# SCH_Smart-Traffic-Light_2025-03-28_1.net
KiCad netlist of a schematic drawn in EasyEDA
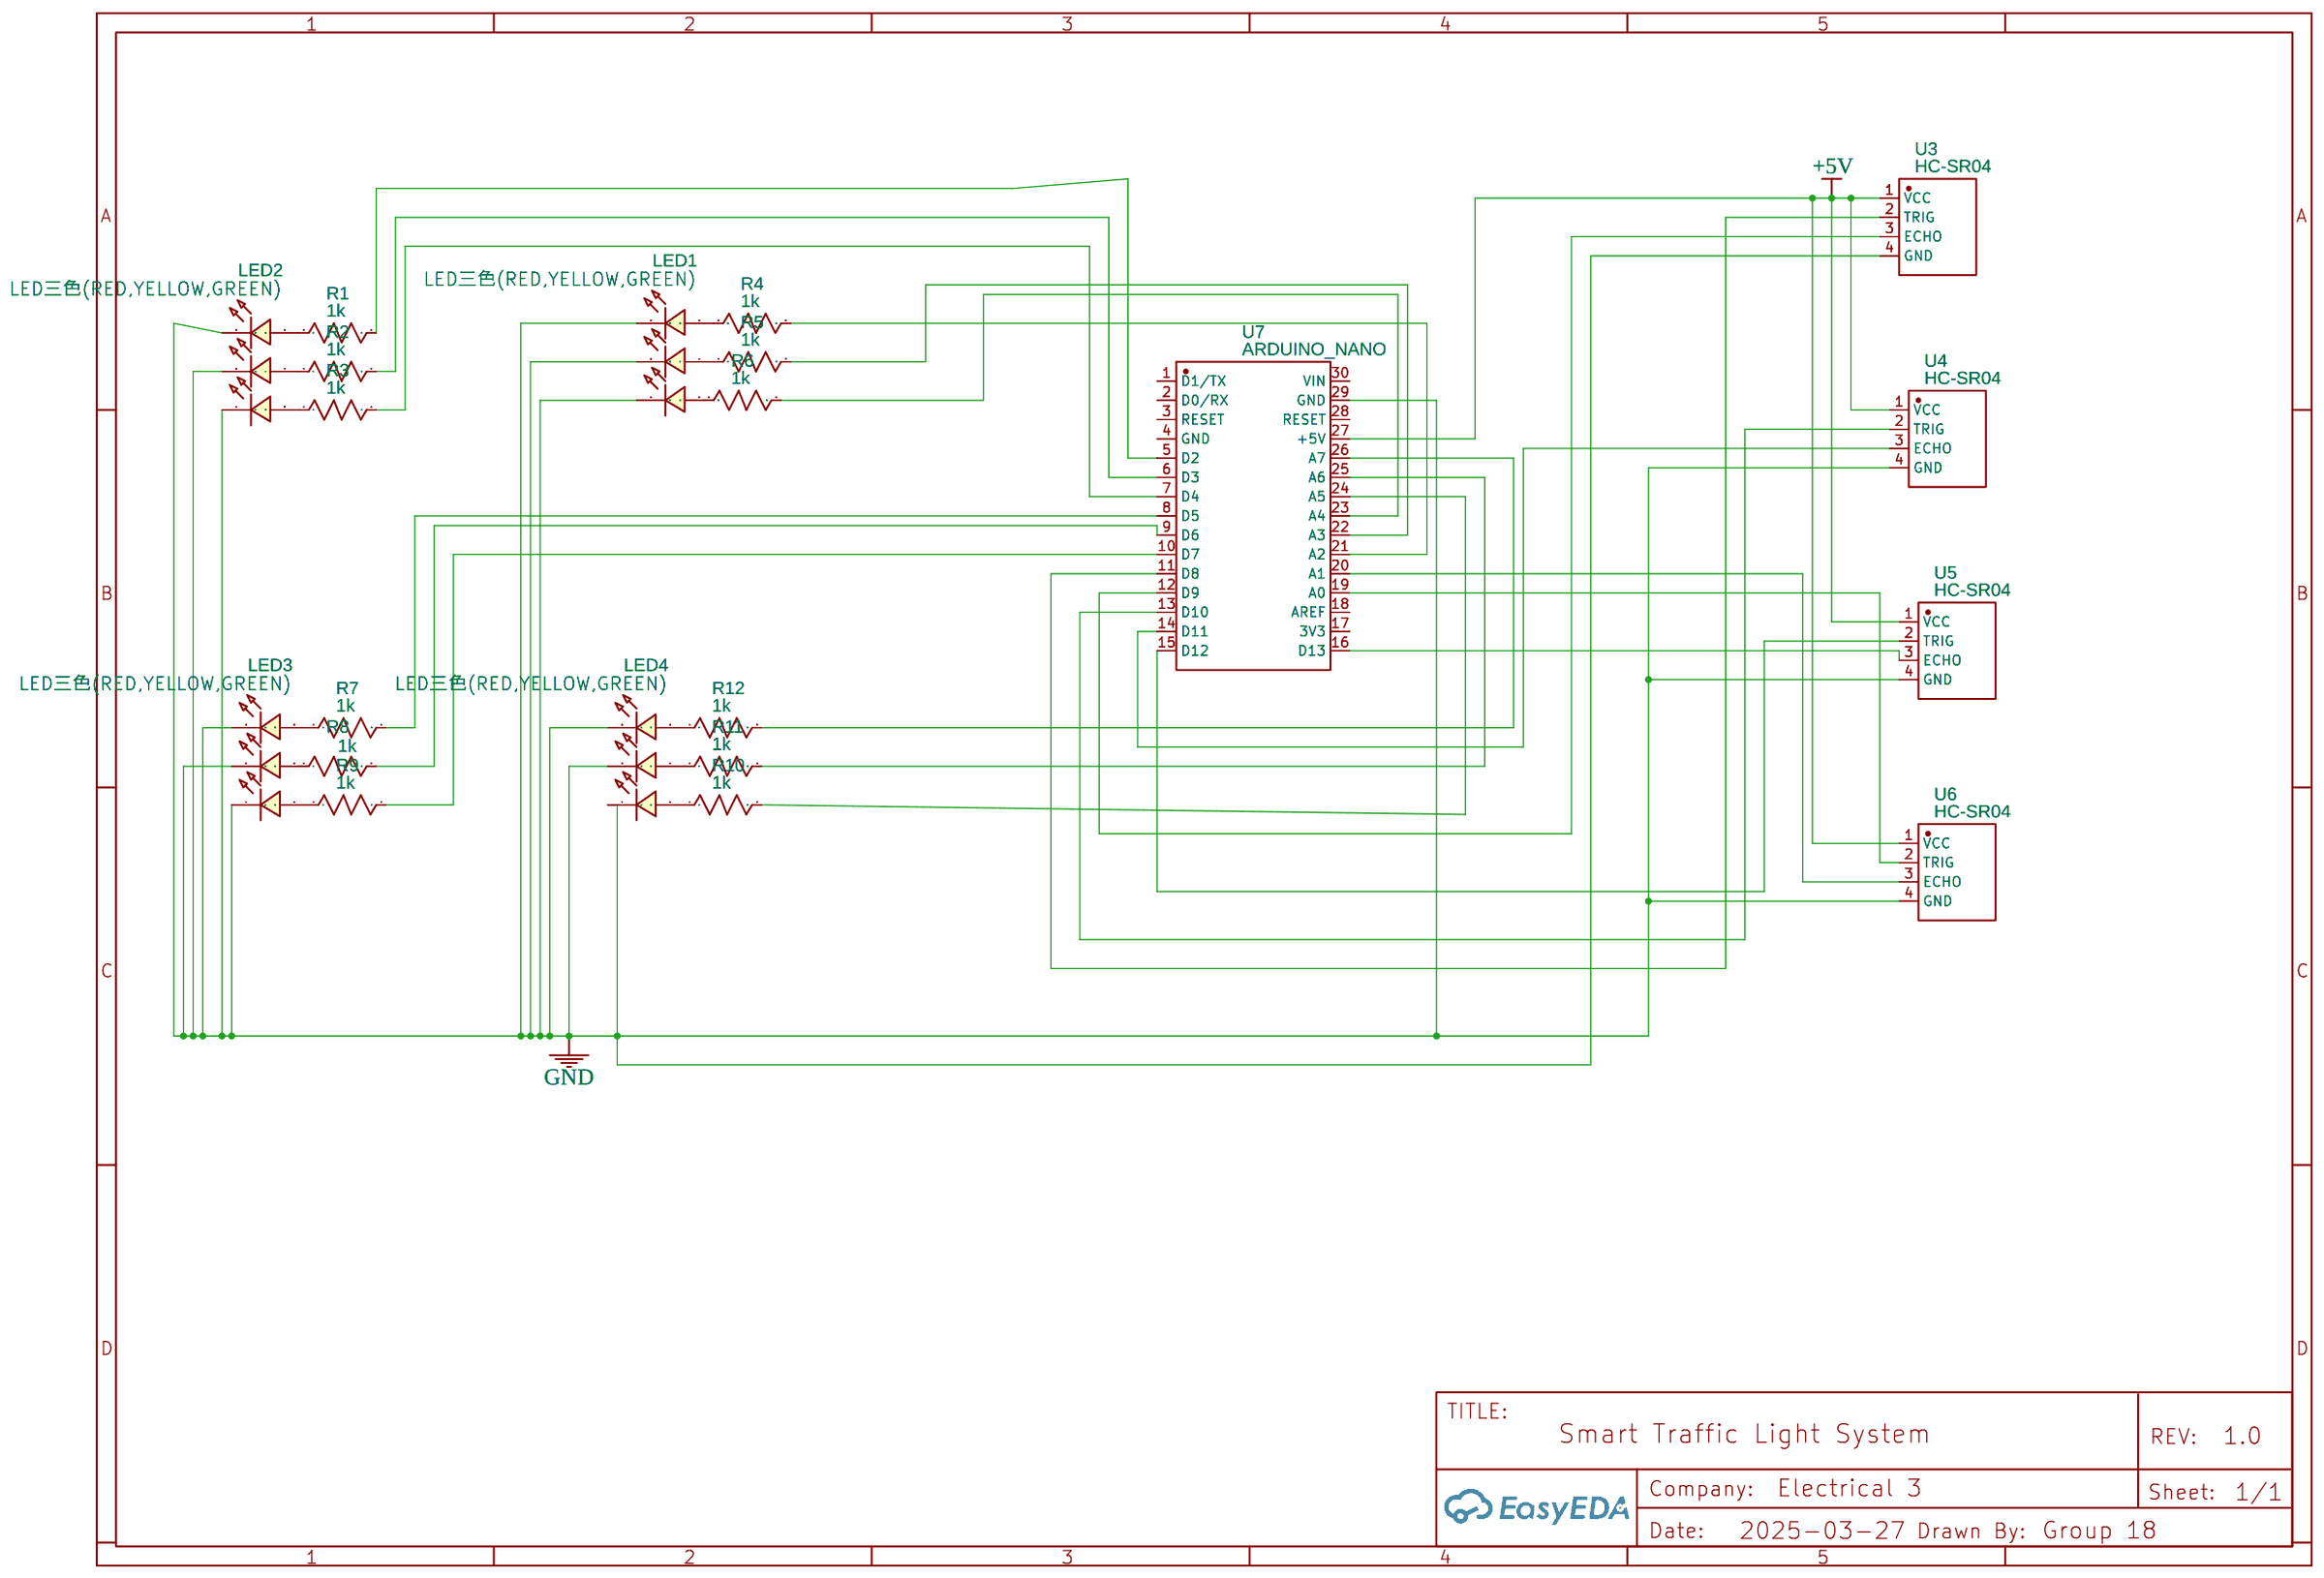
[diagram p0: schematic sheet]

(export (version "E")
  (design (tool "Eeschema 10.0.6"))
  (components
    (comp (ref "LED1")
      (value "LED三色(RED,YELLOW,GREEN)")
      (fields (field (name "Manufacturer Part") "LED三色(Red,Yellow,Green)"))
      (libsource (lib "") (part "LED三色(RED,YELLOW,GREEN)"))
    )
    (comp (ref "LED2")
      (value "LED三色(RED,YELLOW,GREEN)")
      (fields (field (name "Manufacturer Part") "LED三色(Red,Yellow,Green)"))
      (libsource (lib "") (part "LED三色(RED,YELLOW,GREEN)"))
    )
    (comp (ref "LED3")
      (value "LED三色(RED,YELLOW,GREEN)")
      (fields (field (name "Manufacturer Part") "LED三色(Red,Yellow,Green)"))
      (libsource (lib "") (part "LED三色(RED,YELLOW,GREEN)"))
    )
    (comp (ref "LED4")
      (value "LED三色(RED,YELLOW,GREEN)")
      (fields (field (name "Manufacturer Part") "LED三色(Red,Yellow,Green)"))
      (libsource (lib "") (part "LED三色(RED,YELLOW,GREEN)"))
    )
    (comp (ref "R1") (value "1k") (libsource (lib "") (part "R_0603_US")))
    (comp (ref "R2") (value "1k") (libsource (lib "") (part "R_0603_US")))
    (comp (ref "R3") (value "1k") (libsource (lib "") (part "R_0603_US")))
    (comp (ref "R4") (value "1k") (libsource (lib "") (part "R_0603_US")))
    (comp (ref "R5") (value "1k") (libsource (lib "") (part "R_0603_US")))
    (comp (ref "R6") (value "1k") (libsource (lib "") (part "R_0603_US")))
    (comp (ref "R7") (value "1k") (libsource (lib "") (part "R_0603_US")))
    (comp (ref "R8") (value "1k") (libsource (lib "") (part "R_0603_US")))
    (comp (ref "R9") (value "1k") (libsource (lib "") (part "R_0603_US")))
    (comp (ref "R10") (value "1k") (libsource (lib "") (part "R_0603_US")))
    (comp (ref "R11") (value "1k") (libsource (lib "") (part "R_0603_US")))
    (comp (ref "R12") (value "1k") (libsource (lib "") (part "R_0603_US")))
    (comp (ref "U3")
      (value "HC-SR04")
      (fields (field (name "Manufacturer") "Universal Microelectronics"))
      (libsource (lib "") (part "HC-SR04"))
    )
    (comp (ref "U4")
      (value "HC-SR04")
      (fields (field (name "Manufacturer") "Universal Microelectronics"))
      (libsource (lib "") (part "HC-SR04"))
    )
    (comp (ref "U5")
      (value "HC-SR04")
      (fields (field (name "Manufacturer") "Universal Microelectronics"))
      (libsource (lib "") (part "HC-SR04"))
    )
    (comp (ref "U6")
      (value "HC-SR04")
      (fields (field (name "Manufacturer") "Universal Microelectronics"))
      (libsource (lib "") (part "HC-SR04"))
    )
    (comp (ref "U7") (value "ARDUINO_NANO") (libsource (lib "") (part "ARDUINO_NANO")))
  )
  (nets
    (net (code "1") (name "+5V") (class "Default")
      (node (ref "U3") (pin "1") (pinfunction "VCC_1") (pintype "unspecified"))
      (node (ref "U4") (pin "1") (pinfunction "VCC_1") (pintype "unspecified"))
      (node (ref "U5") (pin "1") (pinfunction "VCC_1") (pintype "unspecified"))
      (node (ref "U6") (pin "1") (pinfunction "VCC_1") (pintype "unspecified"))
      (node (ref "U7") (pin "27") (pinfunction "+5V_27") (pintype "unspecified"))
    )
    (net (code "2") (name "GND") (class "Default")
      (node (ref "LED1") (pin "1") (pinfunction "1_1") (pintype "unspecified"))
      (node (ref "LED1") (pin "3") (pinfunction "3_3") (pintype "unspecified"))
      (node (ref "LED1") (pin "5") (pinfunction "5_5") (pintype "unspecified"))
      (node (ref "LED2") (pin "1") (pinfunction "1_1") (pintype "unspecified"))
      (node (ref "LED2") (pin "3") (pinfunction "3_3") (pintype "unspecified"))
      (node (ref "LED2") (pin "5") (pinfunction "5_5") (pintype "unspecified"))
      (node (ref "LED3") (pin "1") (pinfunction "1_1") (pintype "unspecified"))
      (node (ref "LED3") (pin "3") (pinfunction "3_3") (pintype "unspecified"))
      (node (ref "LED3") (pin "5") (pinfunction "5_5") (pintype "unspecified"))
      (node (ref "LED4") (pin "1") (pinfunction "1_1") (pintype "unspecified"))
      (node (ref "LED4") (pin "3") (pinfunction "3_3") (pintype "unspecified"))
      (node (ref "LED4") (pin "5") (pinfunction "5_5") (pintype "unspecified"))
      (node (ref "U3") (pin "4") (pinfunction "GND_4") (pintype "unspecified"))
      (node (ref "U4") (pin "4") (pinfunction "GND_4") (pintype "unspecified"))
      (node (ref "U5") (pin "4") (pinfunction "GND_4") (pintype "unspecified"))
      (node (ref "U6") (pin "4") (pinfunction "GND_4") (pintype "unspecified"))
      (node (ref "U7") (pin "29") (pinfunction "GND_29") (pintype "unspecified"))
    )
    (net (code "3") (name "Net-(LED1-Pad4)") (class "Default")
      (node (ref "LED1") (pin "4") (pinfunction "4_4") (pintype "unspecified"))
      (node (ref "R5") (pin "1") (pinfunction "1_1") (pintype "unspecified"))
    )
    (net (code "4") (name "Net-(LED1-Pad6)") (class "Default")
      (node (ref "LED1") (pin "6") (pinfunction "6_6") (pintype "unspecified"))
      (node (ref "R4") (pin "1") (pinfunction "1_1") (pintype "unspecified"))
    )
    (net (code "5") (name "Net-(LED2-Pad2)") (class "Default")
      (node (ref "LED2") (pin "2") (pinfunction "2_2") (pintype "unspecified"))
      (node (ref "R3") (pin "1") (pinfunction "1_1") (pintype "unspecified"))
    )
    (net (code "6") (name "Net-(LED2-Pad4)") (class "Default")
      (node (ref "LED2") (pin "4") (pinfunction "4_4") (pintype "unspecified"))
      (node (ref "R2") (pin "1") (pinfunction "1_1") (pintype "unspecified"))
    )
    (net (code "7") (name "Net-(LED2-Pad6)") (class "Default")
      (node (ref "LED2") (pin "6") (pinfunction "6_6") (pintype "unspecified"))
      (node (ref "R1") (pin "1") (pinfunction "1_1") (pintype "unspecified"))
    )
    (net (code "8") (name "Net-(LED3-Pad2)") (class "Default")
      (node (ref "LED3") (pin "2") (pinfunction "2_2") (pintype "unspecified"))
      (node (ref "R9") (pin "1") (pinfunction "1_1") (pintype "unspecified"))
    )
    (net (code "9") (name "Net-(LED3-Pad6)") (class "Default")
      (node (ref "LED3") (pin "6") (pinfunction "6_6") (pintype "unspecified"))
      (node (ref "R7") (pin "1") (pinfunction "1_1") (pintype "unspecified"))
    )
    (net (code "10") (name "Net-(LED4-Pad2)") (class "Default")
      (node (ref "LED4") (pin "2") (pinfunction "2_2") (pintype "unspecified"))
      (node (ref "R10") (pin "1") (pinfunction "1_1") (pintype "unspecified"))
    )
    (net (code "11") (name "Net-(LED4-Pad4)") (class "Default")
      (node (ref "LED4") (pin "4") (pinfunction "4_4") (pintype "unspecified"))
      (node (ref "R11") (pin "1") (pinfunction "1_1") (pintype "unspecified"))
    )
    (net (code "12") (name "Net-(LED4-Pad6)") (class "Default")
      (node (ref "LED4") (pin "6") (pinfunction "6_6") (pintype "unspecified"))
      (node (ref "R12") (pin "1") (pinfunction "1_1") (pintype "unspecified"))
    )
    (net (code "13") (name "Net-(U3-ECHO)") (class "Default")
      (node (ref "U3") (pin "3") (pinfunction "ECHO_3") (pintype "unspecified"))
      (node (ref "U7") (pin "12") (pinfunction "D9_12") (pintype "unspecified"))
    )
    (net (code "14") (name "Net-(U3-TRIG)") (class "Default")
      (node (ref "U3") (pin "2") (pinfunction "TRIG_2") (pintype "unspecified"))
      (node (ref "U7") (pin "11") (pinfunction "D8_11") (pintype "unspecified"))
    )
    (net (code "15") (name "Net-(U4-ECHO)") (class "Default")
      (node (ref "U4") (pin "3") (pinfunction "ECHO_3") (pintype "unspecified"))
      (node (ref "U7") (pin "14") (pinfunction "D11_14") (pintype "unspecified"))
    )
    (net (code "16") (name "Net-(U4-TRIG)") (class "Default")
      (node (ref "U4") (pin "2") (pinfunction "TRIG_2") (pintype "unspecified"))
      (node (ref "U7") (pin "13") (pinfunction "D10_13") (pintype "unspecified"))
    )
    (net (code "17") (name "Net-(U5-ECHO)") (class "Default")
      (node (ref "U5") (pin "3") (pinfunction "ECHO_3") (pintype "unspecified"))
      (node (ref "U7") (pin "16") (pinfunction "D13_16") (pintype "unspecified"))
    )
    (net (code "18") (name "Net-(U5-TRIG)") (class "Default")
      (node (ref "U5") (pin "2") (pinfunction "TRIG_2") (pintype "unspecified"))
      (node (ref "U7") (pin "15") (pinfunction "D12_15") (pintype "unspecified"))
    )
    (net (code "19") (name "Net-(U6-ECHO)") (class "Default")
      (node (ref "U6") (pin "3") (pinfunction "ECHO_3") (pintype "unspecified"))
      (node (ref "U7") (pin "20") (pinfunction "A1_20") (pintype "unspecified"))
    )
    (net (code "20") (name "Net-(U6-TRIG)") (class "Default")
      (node (ref "U6") (pin "2") (pinfunction "TRIG_2") (pintype "unspecified"))
      (node (ref "U7") (pin "19") (pinfunction "A0_19") (pintype "unspecified"))
    )
    (net (code "21") (name "Net-(U7-A2)") (class "Default")
      (node (ref "R4") (pin "2") (pinfunction "2_2") (pintype "unspecified"))
      (node (ref "U7") (pin "21") (pinfunction "A2_21") (pintype "unspecified"))
    )
    (net (code "22") (name "Net-(U7-A3)") (class "Default")
      (node (ref "R5") (pin "2") (pinfunction "2_2") (pintype "unspecified"))
      (node (ref "U7") (pin "22") (pinfunction "A3_22") (pintype "unspecified"))
    )
    (net (code "23") (name "Net-(U7-A4)") (class "Default")
      (node (ref "R6") (pin "2") (pinfunction "2_2") (pintype "unspecified"))
      (node (ref "U7") (pin "23") (pinfunction "A4_23") (pintype "unspecified"))
    )
    (net (code "24") (name "Net-(U7-A5)") (class "Default")
      (node (ref "R10") (pin "2") (pinfunction "2_2") (pintype "unspecified"))
      (node (ref "U7") (pin "24") (pinfunction "A5_24") (pintype "unspecified"))
    )
    (net (code "25") (name "Net-(U7-A6)") (class "Default")
      (node (ref "R11") (pin "2") (pinfunction "2_2") (pintype "unspecified"))
      (node (ref "U7") (pin "25") (pinfunction "A6_25") (pintype "unspecified"))
    )
    (net (code "26") (name "Net-(U7-A7)") (class "Default")
      (node (ref "R12") (pin "2") (pinfunction "2_2") (pintype "unspecified"))
      (node (ref "U7") (pin "26") (pinfunction "A7_26") (pintype "unspecified"))
    )
    (net (code "27") (name "Net-(U7-D2)") (class "Default")
      (node (ref "R1") (pin "2") (pinfunction "2_2") (pintype "unspecified"))
      (node (ref "U7") (pin "5") (pinfunction "D2_5") (pintype "unspecified"))
    )
    (net (code "28") (name "Net-(U7-D3)") (class "Default")
      (node (ref "R2") (pin "2") (pinfunction "2_2") (pintype "unspecified"))
      (node (ref "U7") (pin "6") (pinfunction "D3_6") (pintype "unspecified"))
    )
    (net (code "29") (name "Net-(U7-D4)") (class "Default")
      (node (ref "R3") (pin "2") (pinfunction "2_2") (pintype "unspecified"))
      (node (ref "U7") (pin "7") (pinfunction "D4_7") (pintype "unspecified"))
    )
    (net (code "30") (name "Net-(U7-D5)") (class "Default")
      (node (ref "R7") (pin "2") (pinfunction "2_2") (pintype "unspecified"))
      (node (ref "U7") (pin "8") (pinfunction "D5_8") (pintype "unspecified"))
    )
    (net (code "31") (name "Net-(U7-D6)") (class "Default")
      (node (ref "R8") (pin "2") (pinfunction "2_2") (pintype "unspecified"))
      (node (ref "U7") (pin "9") (pinfunction "D6_9") (pintype "unspecified"))
    )
    (net (code "32") (name "Net-(U7-D7)") (class "Default")
      (node (ref "R9") (pin "2") (pinfunction "2_2") (pintype "unspecified"))
      (node (ref "U7") (pin "10") (pinfunction "D7_10") (pintype "unspecified"))
    )
    (net (code "33") (name "unconnected-(LED1-Pad2)") (class "Default")
      (node (ref "LED1") (pin "2") (pinfunction "2_2") (pintype "unspecified"))
    )
    (net (code "34") (name "unconnected-(LED3-Pad4)") (class "Default")
      (node (ref "LED3") (pin "4") (pinfunction "4_4") (pintype "unspecified"))
    )
    (net (code "35") (name "unconnected-(R6-Pad1)") (class "Default")
      (node (ref "R6") (pin "1") (pinfunction "1_1") (pintype "unspecified"))
    )
    (net (code "36") (name "unconnected-(R8-Pad1)") (class "Default")
      (node (ref "R8") (pin "1") (pinfunction "1_1") (pintype "unspecified"))
    )
    (net (code "37") (name "unconnected-(U7-3V3-Pad17)") (class "Default")
      (node (ref "U7") (pin "17") (pinfunction "3V3_17") (pintype "unspecified"))
    )
    (net (code "38") (name "unconnected-(U7-AREF-Pad18)") (class "Default")
      (node (ref "U7") (pin "18") (pinfunction "AREF_18") (pintype "unspecified"))
    )
    (net (code "39") (name "unconnected-(U7-D0{slash}RX-Pad2)") (class "Default")
      (node (ref "U7") (pin "2") (pinfunction "D0/RX_2") (pintype "unspecified"))
    )
    (net (code "40") (name "unconnected-(U7-D1{slash}TX-Pad1)") (class "Default")
      (node (ref "U7") (pin "1") (pinfunction "D1/TX_1") (pintype "unspecified"))
    )
    (net (code "41") (name "unconnected-(U7-GND-Pad4)") (class "Default")
      (node (ref "U7") (pin "4") (pinfunction "GND_4") (pintype "unspecified"))
    )
    (net (code "42") (name "unconnected-(U7-RESET-Pad3)") (class "Default")
      (node (ref "U7") (pin "3") (pinfunction "RESET_3") (pintype "unspecified"))
    )
    (net (code "43") (name "unconnected-(U7-RESET-Pad28)") (class "Default")
      (node (ref "U7") (pin "28") (pinfunction "RESET_28") (pintype "unspecified"))
    )
    (net (code "44") (name "unconnected-(U7-VIN-Pad30)") (class "Default")
      (node (ref "U7") (pin "30") (pinfunction "VIN_30") (pintype "unspecified"))
    )
  )
)
